# avionics_system.net
KiCad netlist of a schematic drawn in EasyEDA
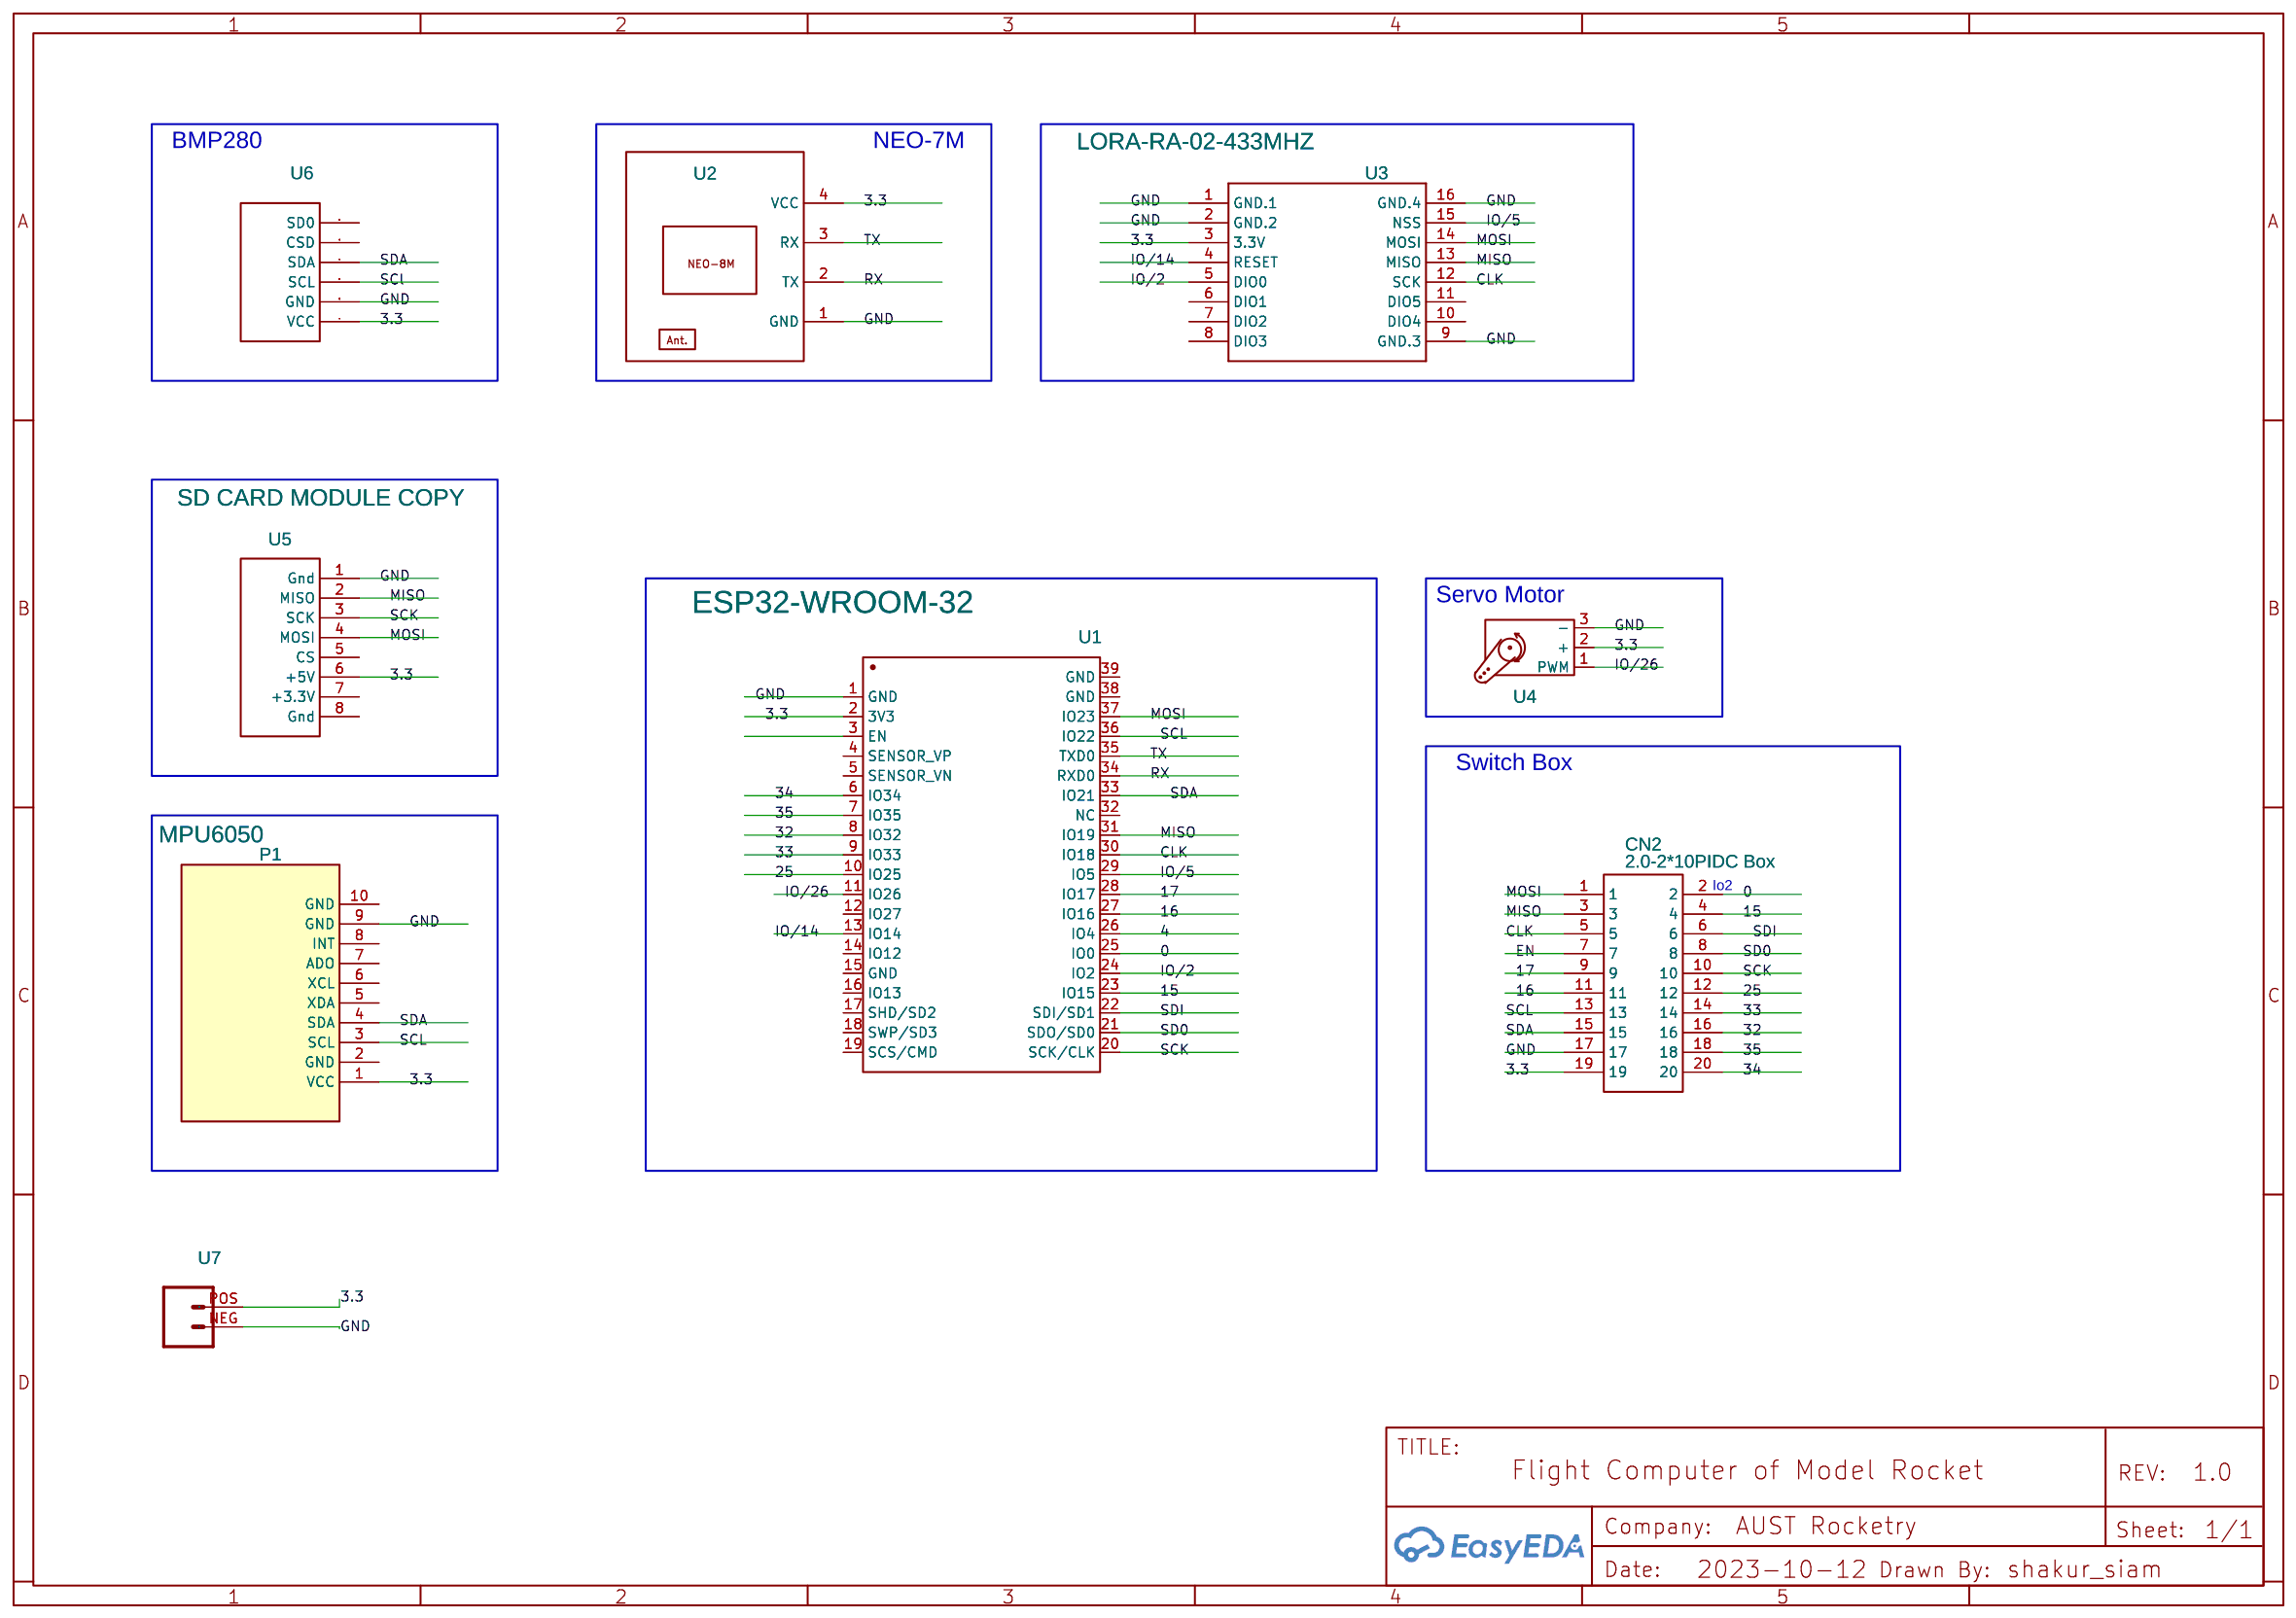
[diagram p0: schematic sheet]

(export (version "E")
  (design (tool "Eeschema 10.0.6"))
  (components
    (comp (ref "CN2")
      (value "2.0-2*10PIDC Box")
      (fields (field (name "Manufacturer Part") "2.0-2*10P简牛") (field (name "Manufacturer") "BOOMELE(博穆精密)"))
      (libsource (lib "") (part "2.0-2*10PIDC Box"))
    )
    (comp (ref "P1") (value "MPU6050") (libsource (lib "") (part "MPU6050")))
    (comp (ref "U1")
      (value "ESP32-WROOM-32")
      (fields
        (field (name "Manufacturer Part") "ESP32-WROOM-32-N4")
        (field (name "Manufacturer") "ESPRESSIF(乐鑫)")
      )
      (libsource (lib "") (part "ESP32-WROOM-32"))
    )
    (comp (ref "U2") (value "~") (libsource (lib "") (part "GY-GPSV3-NEO-copy")))
    (comp (ref "U3") (value "LORA-RA-02-433MHZ") (libsource (lib "") (part "LORA-RA-02-433MHZ")))
    (comp (ref "U4") (value "~") (libsource (lib "") (part "KKTL-Motor-Servo-01")))
    (comp (ref "U5")
      (value "SD CARD MODULE COPY")
      (fields (field (name "Manufacturer Part") "sd card module"))
      (libsource (lib "") (part "SD CARD MODULE COPY"))
    )
    (comp (ref "U6") (value "NO") (libsource (lib "") (part "BMP280")))
    (comp (ref "U7") (value "~") (libsource (lib "") (part "TIMWOO-CONNECTORS_M02SNAP_CONN")))
  )
  (nets
    (net (code "1") (name "/0") (class "Default")
      (node (ref "CN2") (pin "2") (pinfunction "2_2") (pintype "unspecified"))
      (node (ref "U1") (pin "25") (pinfunction "IO0_25") (pintype "unspecified"))
    )
    (net (code "2") (name "/3.3") (class "Default")
      (node (ref "CN2") (pin "19") (pinfunction "19_19") (pintype "unspecified"))
      (node (ref "P1") (pin "1") (pinfunction "VCC_1") (pintype "unspecified"))
      (node (ref "U1") (pin "2") (pinfunction "3V3_2") (pintype "unspecified"))
      (node (ref "U2") (pin "4") (pinfunction "VCC_4") (pintype "unspecified"))
      (node (ref "U3") (pin "3") (pinfunction "3.3V_3") (pintype "passive"))
      (node (ref "U4") (pin "2") (pinfunction "+_2") (pintype "unspecified"))
      (node (ref "U5") (pin "6") (pinfunction "+5V_6") (pintype "unspecified"))
      (node (ref "U6") (pin "7") (pinfunction "VCC_7") (pintype "unspecified"))
      (node (ref "U7") (pin "POS") (pinfunction "2_POS") (pintype "bidirectional"))
    )
    (net (code "3") (name "/4") (class "Default")
      (node (ref "U1") (pin "26") (pinfunction "IO4_26") (pintype "unspecified"))
    )
    (net (code "4") (name "/15") (class "Default")
      (node (ref "CN2") (pin "4") (pinfunction "4_4") (pintype "unspecified"))
      (node (ref "U1") (pin "23") (pinfunction "IO15_23") (pintype "unspecified"))
    )
    (net (code "5") (name "/16") (class "Default")
      (node (ref "CN2") (pin "11") (pinfunction "11_11") (pintype "unspecified"))
      (node (ref "U1") (pin "27") (pinfunction "IO16_27") (pintype "unspecified"))
    )
    (net (code "6") (name "/17") (class "Default")
      (node (ref "CN2") (pin "9") (pinfunction "9_9") (pintype "unspecified"))
      (node (ref "U1") (pin "28") (pinfunction "IO17_28") (pintype "unspecified"))
    )
    (net (code "7") (name "/25") (class "Default")
      (node (ref "CN2") (pin "12") (pinfunction "12_12") (pintype "unspecified"))
      (node (ref "U1") (pin "10") (pinfunction "IO25_10") (pintype "unspecified"))
    )
    (net (code "8") (name "/32") (class "Default")
      (node (ref "CN2") (pin "16") (pinfunction "16_16") (pintype "unspecified"))
      (node (ref "U1") (pin "8") (pinfunction "IO32_8") (pintype "unspecified"))
    )
    (net (code "9") (name "/33") (class "Default")
      (node (ref "CN2") (pin "14") (pinfunction "14_14") (pintype "unspecified"))
      (node (ref "U1") (pin "9") (pinfunction "IO33_9") (pintype "unspecified"))
    )
    (net (code "10") (name "/34") (class "Default")
      (node (ref "CN2") (pin "20") (pinfunction "20_20") (pintype "unspecified"))
      (node (ref "U1") (pin "6") (pinfunction "IO34_6") (pintype "unspecified"))
    )
    (net (code "11") (name "/35") (class "Default")
      (node (ref "CN2") (pin "18") (pinfunction "18_18") (pintype "unspecified"))
      (node (ref "U1") (pin "7") (pinfunction "IO35_7") (pintype "unspecified"))
    )
    (net (code "12") (name "/CLK") (class "Default")
      (node (ref "CN2") (pin "5") (pinfunction "5_5") (pintype "unspecified"))
      (node (ref "U1") (pin "30") (pinfunction "IO18_30") (pintype "unspecified"))
      (node (ref "U3") (pin "12") (pinfunction "SCK_12") (pintype "unspecified"))
    )
    (net (code "13") (name "/EN") (class "Default")
      (node (ref "CN2") (pin "7") (pinfunction "7_7") (pintype "unspecified"))
    )
    (net (code "14") (name "/GND") (class "Default")
      (node (ref "CN2") (pin "17") (pinfunction "17_17") (pintype "unspecified"))
      (node (ref "P1") (pin "9") (pinfunction "GND_9") (pintype "unspecified"))
      (node (ref "U1") (pin "1") (pinfunction "GND_1") (pintype "unspecified"))
      (node (ref "U2") (pin "1") (pinfunction "GND_1") (pintype "unspecified"))
      (node (ref "U3") (pin "1") (pinfunction "GND.1_1") (pintype "passive"))
      (node (ref "U3") (pin "16") (pinfunction "GND.4_16") (pintype "passive"))
      (node (ref "U3") (pin "2") (pinfunction "GND.2_2") (pintype "passive"))
      (node (ref "U3") (pin "9") (pinfunction "GND.3_9") (pintype "passive"))
      (node (ref "U4") (pin "3") (pinfunction "-_3") (pintype "unspecified"))
      (node (ref "U5") (pin "1") (pinfunction "Gnd_1") (pintype "unspecified"))
      (node (ref "U6") (pin "6") (pinfunction "GND_6") (pintype "unspecified"))
      (node (ref "U7") (pin "NEG") (pinfunction "1_NEG") (pintype "bidirectional"))
    )
    (net (code "15") (name "/IO{slash}2") (class "Default")
      (node (ref "U1") (pin "24") (pinfunction "IO2_24") (pintype "unspecified"))
      (node (ref "U3") (pin "5") (pinfunction "DIO0_5") (pintype "unspecified"))
    )
    (net (code "16") (name "/IO{slash}5") (class "Default")
      (node (ref "U1") (pin "29") (pinfunction "IO5_29") (pintype "unspecified"))
      (node (ref "U3") (pin "15") (pinfunction "NSS_15") (pintype "unspecified"))
    )
    (net (code "17") (name "/IO{slash}14") (class "Default")
      (node (ref "U1") (pin "13") (pinfunction "IO14_13") (pintype "unspecified"))
      (node (ref "U3") (pin "4") (pinfunction "RESET_4") (pintype "unspecified"))
    )
    (net (code "18") (name "/IO{slash}26") (class "Default")
      (node (ref "U1") (pin "11") (pinfunction "IO26_11") (pintype "unspecified"))
      (node (ref "U4") (pin "1") (pinfunction "PWM_1") (pintype "unspecified"))
    )
    (net (code "19") (name "/MISO") (class "Default")
      (node (ref "CN2") (pin "3") (pinfunction "3_3") (pintype "unspecified"))
      (node (ref "U1") (pin "31") (pinfunction "IO19_31") (pintype "unspecified"))
      (node (ref "U3") (pin "13") (pinfunction "MISO_13") (pintype "unspecified"))
      (node (ref "U5") (pin "2") (pinfunction "MISO_2") (pintype "unspecified"))
    )
    (net (code "20") (name "/MOSI") (class "Default")
      (node (ref "CN2") (pin "1") (pinfunction "1_1") (pintype "unspecified"))
      (node (ref "U1") (pin "37") (pinfunction "IO23_37") (pintype "unspecified"))
      (node (ref "U3") (pin "14") (pinfunction "MOSI_14") (pintype "unspecified"))
      (node (ref "U5") (pin "4") (pinfunction "MOSI_4") (pintype "unspecified"))
    )
    (net (code "21") (name "/RX") (class "Default")
      (node (ref "U1") (pin "34") (pinfunction "RXD0_34") (pintype "unspecified"))
      (node (ref "U2") (pin "2") (pinfunction "TX_2") (pintype "unspecified"))
    )
    (net (code "22") (name "/SCK") (class "Default")
      (node (ref "CN2") (pin "10") (pinfunction "10_10") (pintype "unspecified"))
      (node (ref "U1") (pin "20") (pinfunction "SCK/CLK_20") (pintype "unspecified"))
      (node (ref "U5") (pin "3") (pinfunction "SCK_3") (pintype "unspecified"))
    )
    (net (code "23") (name "/SCL") (class "Default")
      (node (ref "CN2") (pin "13") (pinfunction "13_13") (pintype "unspecified"))
      (node (ref "P1") (pin "3") (pinfunction "SCL_3") (pintype "unspecified"))
      (node (ref "U1") (pin "36") (pinfunction "IO22_36") (pintype "unspecified"))
    )
    (net (code "24") (name "/SCl") (class "Default")
      (node (ref "U6") (pin "5") (pinfunction "SCL_5") (pintype "unspecified"))
    )
    (net (code "25") (name "/SD0") (class "Default")
      (node (ref "CN2") (pin "8") (pinfunction "8_8") (pintype "unspecified"))
      (node (ref "U1") (pin "21") (pinfunction "SDO/SD0_21") (pintype "unspecified"))
    )
    (net (code "26") (name "/SDA") (class "Default")
      (node (ref "CN2") (pin "15") (pinfunction "15_15") (pintype "unspecified"))
      (node (ref "P1") (pin "4") (pinfunction "SDA_4") (pintype "unspecified"))
      (node (ref "U1") (pin "33") (pinfunction "IO21_33") (pintype "unspecified"))
      (node (ref "U6") (pin "4") (pinfunction "SDA_4") (pintype "unspecified"))
    )
    (net (code "27") (name "/SDI") (class "Default")
      (node (ref "CN2") (pin "6") (pinfunction "6_6") (pintype "unspecified"))
      (node (ref "U1") (pin "22") (pinfunction "SDI/SD1_22") (pintype "unspecified"))
    )
    (net (code "28") (name "/TX") (class "Default")
      (node (ref "U1") (pin "35") (pinfunction "TXD0_35") (pintype "unspecified"))
      (node (ref "U2") (pin "3") (pinfunction "RX_3") (pintype "unspecified"))
    )
    (net (code "29") (name "unconnected-(P1-ADO-Pad7)") (class "Default")
      (node (ref "P1") (pin "7") (pinfunction "ADO_7") (pintype "unspecified"))
    )
    (net (code "30") (name "unconnected-(P1-GND-Pad2)") (class "Default")
      (node (ref "P1") (pin "2") (pinfunction "GND_2") (pintype "unspecified"))
    )
    (net (code "31") (name "unconnected-(P1-GND-Pad10)") (class "Default")
      (node (ref "P1") (pin "10") (pinfunction "GND_10") (pintype "unspecified"))
    )
    (net (code "32") (name "unconnected-(P1-INT-Pad8)") (class "Default")
      (node (ref "P1") (pin "8") (pinfunction "INT_8") (pintype "unspecified"))
    )
    (net (code "33") (name "unconnected-(P1-XCL-Pad6)") (class "Default")
      (node (ref "P1") (pin "6") (pinfunction "XCL_6") (pintype "unspecified"))
    )
    (net (code "34") (name "unconnected-(P1-XDA-Pad5)") (class "Default")
      (node (ref "P1") (pin "5") (pinfunction "XDA_5") (pintype "unspecified"))
    )
    (net (code "35") (name "unconnected-(U1-EN-Pad3)") (class "Default")
      (node (ref "U1") (pin "3") (pinfunction "EN_3") (pintype "unspecified"))
    )
    (net (code "36") (name "unconnected-(U1-GND-Pad15)") (class "Default")
      (node (ref "U1") (pin "15") (pinfunction "GND_15") (pintype "unspecified"))
    )
    (net (code "37") (name "unconnected-(U1-GND-Pad38)") (class "Default")
      (node (ref "U1") (pin "38") (pinfunction "GND_38") (pintype "unspecified"))
    )
    (net (code "38") (name "unconnected-(U1-GND-Pad39)") (class "Default")
      (node (ref "U1") (pin "39") (pinfunction "GND_39") (pintype "unspecified"))
    )
    (net (code "39") (name "unconnected-(U1-IO12-Pad14)") (class "Default")
      (node (ref "U1") (pin "14") (pinfunction "IO12_14") (pintype "unspecified"))
    )
    (net (code "40") (name "unconnected-(U1-IO13-Pad16)") (class "Default")
      (node (ref "U1") (pin "16") (pinfunction "IO13_16") (pintype "unspecified"))
    )
    (net (code "41") (name "unconnected-(U1-IO27-Pad12)") (class "Default")
      (node (ref "U1") (pin "12") (pinfunction "IO27_12") (pintype "unspecified"))
    )
    (net (code "42") (name "unconnected-(U1-NC-Pad32)") (class "Default")
      (node (ref "U1") (pin "32") (pinfunction "NC_32") (pintype "unspecified"))
    )
    (net (code "43") (name "unconnected-(U1-SCS{slash}CMD-Pad19)") (class "Default")
      (node (ref "U1") (pin "19") (pinfunction "SCS/CMD_19") (pintype "unspecified"))
    )
    (net (code "44") (name "unconnected-(U1-SENSOR_VN-Pad5)") (class "Default")
      (node (ref "U1") (pin "5") (pinfunction "SENSOR_VN_5") (pintype "unspecified"))
    )
    (net (code "45") (name "unconnected-(U1-SENSOR_VP-Pad4)") (class "Default")
      (node (ref "U1") (pin "4") (pinfunction "SENSOR_VP_4") (pintype "unspecified"))
    )
    (net (code "46") (name "unconnected-(U1-SHD{slash}SD2-Pad17)") (class "Default")
      (node (ref "U1") (pin "17") (pinfunction "SHD/SD2_17") (pintype "unspecified"))
    )
    (net (code "47") (name "unconnected-(U1-SWP{slash}SD3-Pad18)") (class "Default")
      (node (ref "U1") (pin "18") (pinfunction "SWP/SD3_18") (pintype "unspecified"))
    )
    (net (code "48") (name "unconnected-(U3-DIO1-Pad6)") (class "Default")
      (node (ref "U3") (pin "6") (pinfunction "DIO1_6") (pintype "unspecified"))
    )
    (net (code "49") (name "unconnected-(U3-DIO2-Pad7)") (class "Default")
      (node (ref "U3") (pin "7") (pinfunction "DIO2_7") (pintype "unspecified"))
    )
    (net (code "50") (name "unconnected-(U3-DIO3-Pad8)") (class "Default")
      (node (ref "U3") (pin "8") (pinfunction "DIO3_8") (pintype "unspecified"))
    )
    (net (code "51") (name "unconnected-(U3-DIO4-Pad10)") (class "Default")
      (node (ref "U3") (pin "10") (pinfunction "DIO4_10") (pintype "unspecified"))
    )
    (net (code "52") (name "unconnected-(U3-DIO5-Pad11)") (class "Default")
      (node (ref "U3") (pin "11") (pinfunction "DIO5_11") (pintype "unspecified"))
    )
    (net (code "53") (name "unconnected-(U5-+3.3V-Pad7)") (class "Default")
      (node (ref "U5") (pin "7") (pinfunction "+3.3V_7") (pintype "unspecified"))
    )
    (net (code "54") (name "unconnected-(U5-CS-Pad5)") (class "Default")
      (node (ref "U5") (pin "5") (pinfunction "CS_5") (pintype "unspecified"))
    )
    (net (code "55") (name "unconnected-(U5-Gnd-Pad8)") (class "Default")
      (node (ref "U5") (pin "8") (pinfunction "Gnd_8") (pintype "unspecified"))
    )
    (net (code "56") (name "unconnected-(U6-CSD-Pad3)") (class "Default")
      (node (ref "U6") (pin "3") (pinfunction "CSD_3") (pintype "unspecified"))
    )
    (net (code "57") (name "unconnected-(U6-SD0-Pad2)") (class "Default")
      (node (ref "U6") (pin "2") (pinfunction "SD0_2") (pintype "unspecified"))
    )
  )
)
